# Sheet.net
KiCad netlist of a schematic drawn in Altium Designer
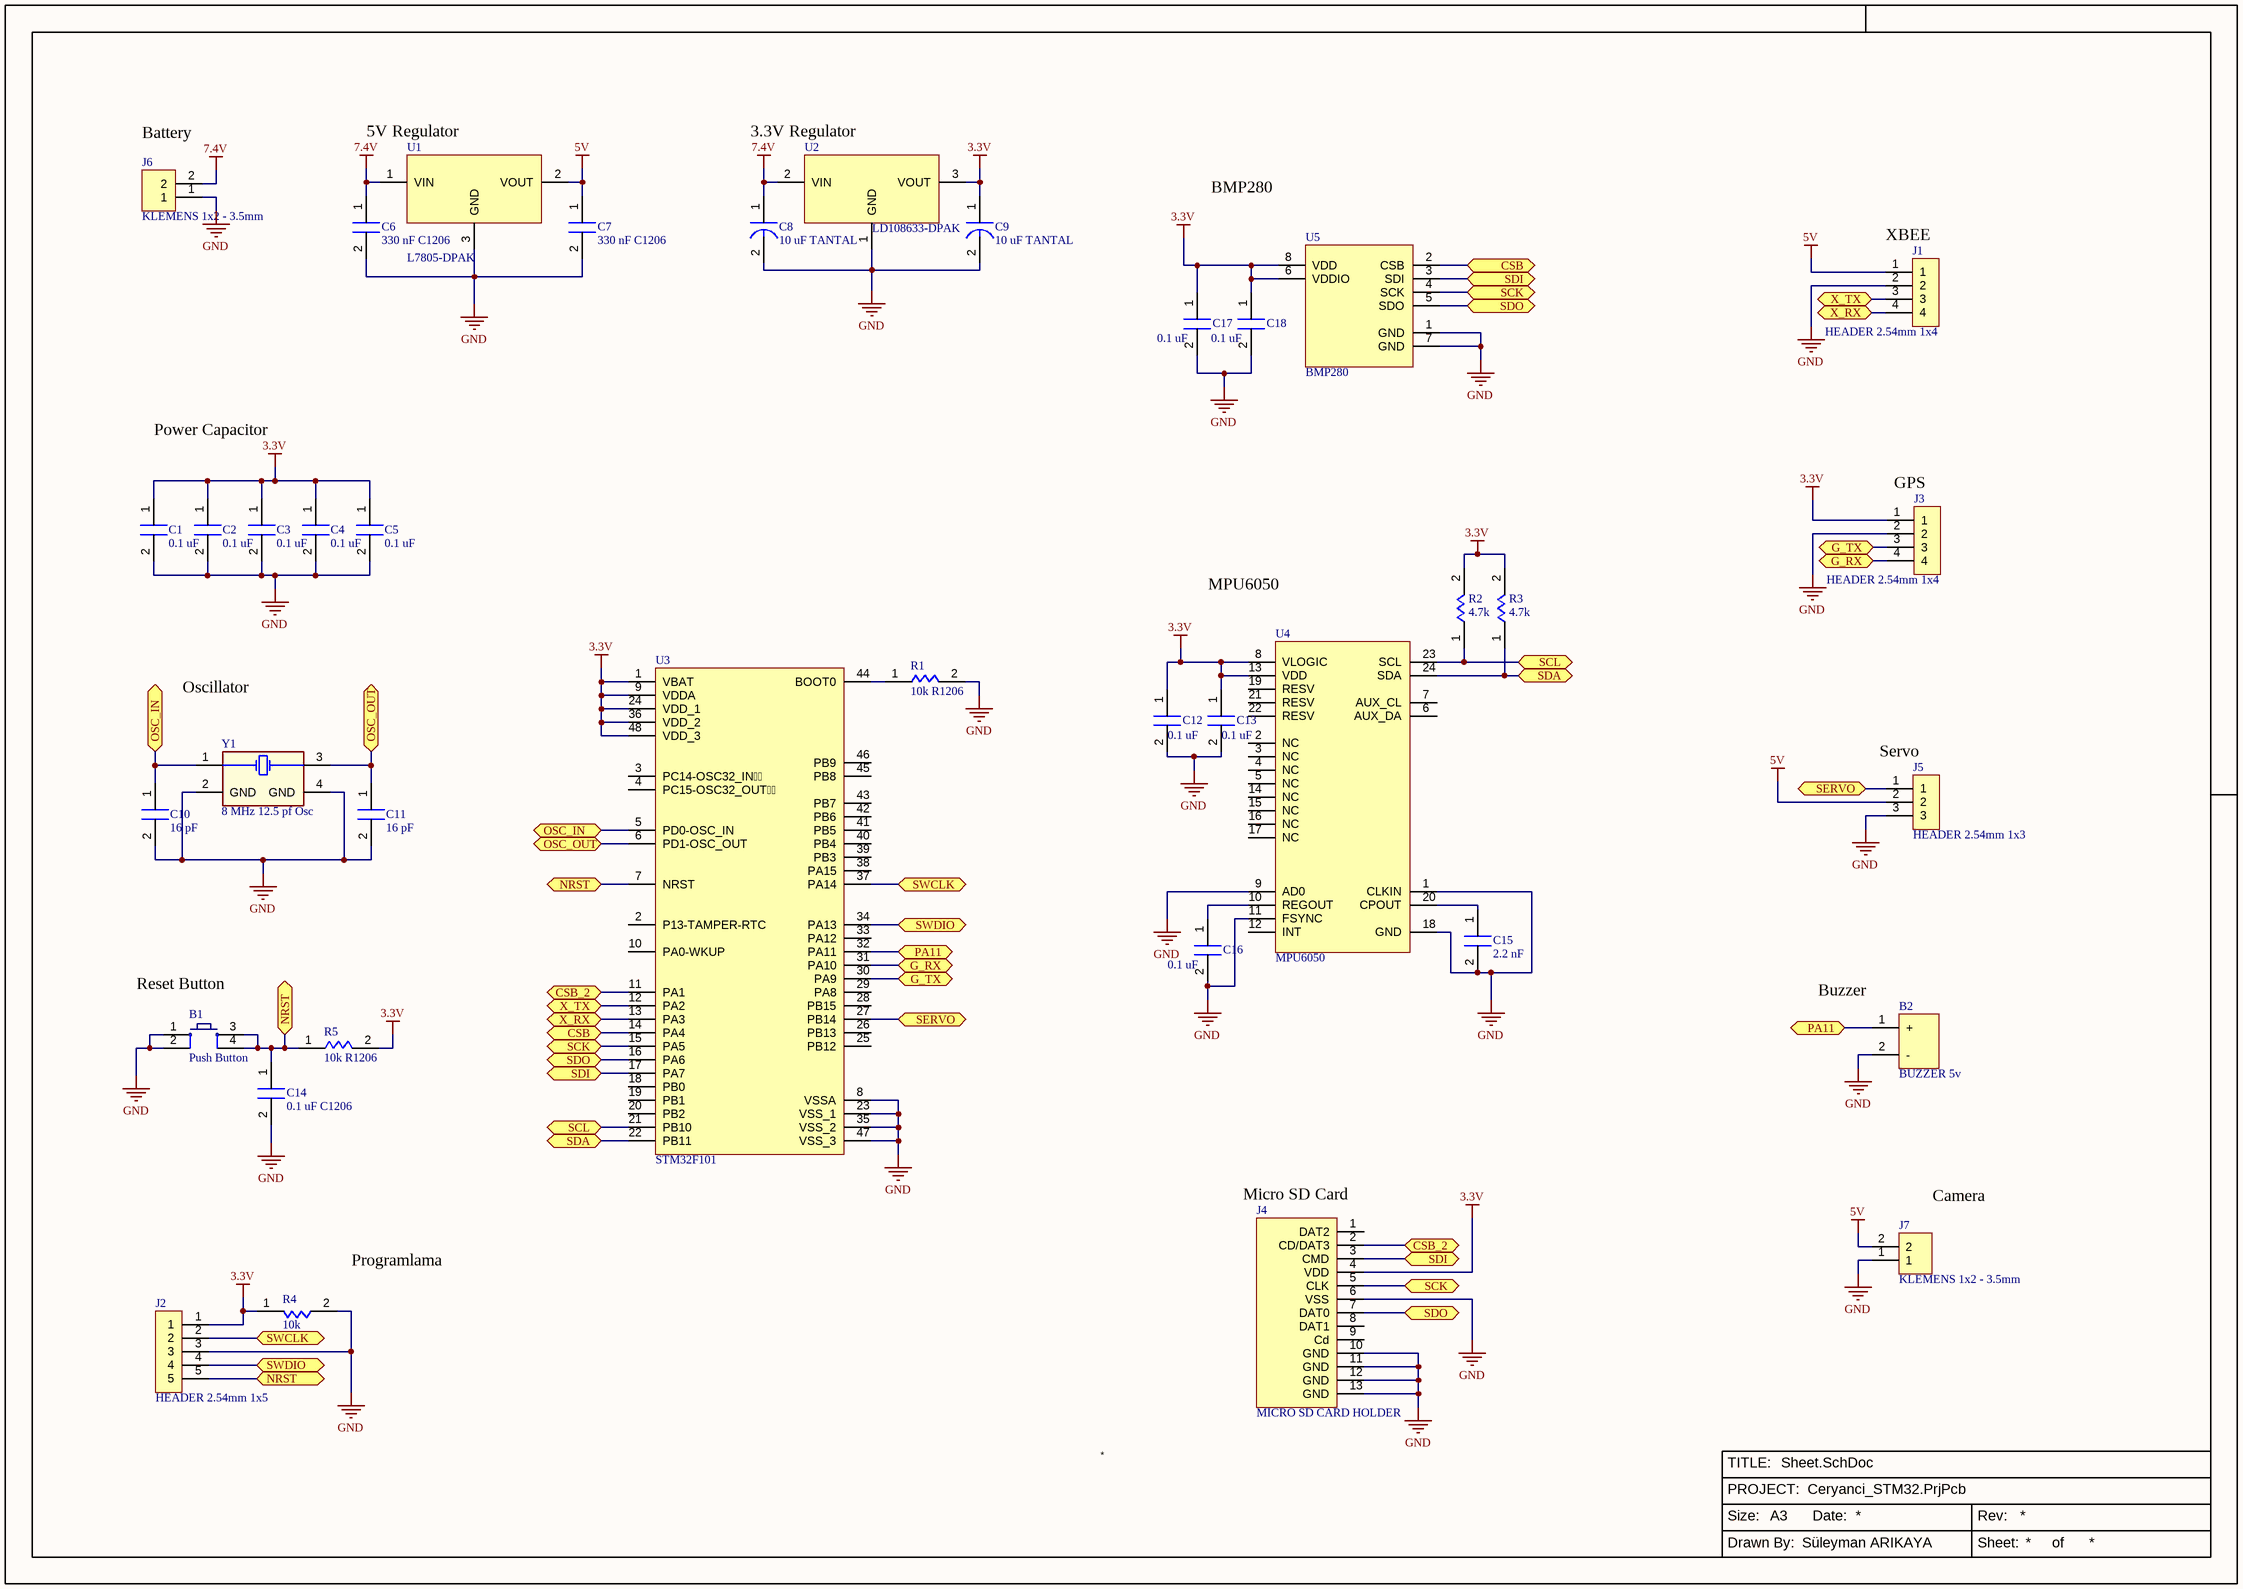
[diagram p0: Sheet.SchDoc]

(export (version "E")
  (design (tool "Eeschema 10.0.6"))
  (components
    (comp (ref "B1")
      (value "Push Button")
      (footprint "PUSB BUTTON-SMD")
      (description "Smd Push Button")
      (libsource (lib "STM32") (part "Push Button"))
    )
    (comp (ref "B2") (value "BUZZER 5v") (footprint "BUZZER 5v") (libsource (lib "STM32") (part "BUZZER 5v")))
    (comp (ref "C1")
      (value "0.1 uF")
      (footprint "C1206")
      (description "0.1 uF C1206")
      (libsource (lib "STM32") (part "0.1 uF C1206"))
    )
    (comp (ref "C2")
      (value "0.1 uF")
      (footprint "C1206")
      (description "0.1 uF C1206")
      (libsource (lib "STM32") (part "0.1 uF C1206"))
    )
    (comp (ref "C3")
      (value "0.1 uF")
      (footprint "C1206")
      (description "0.1 uF C1206")
      (libsource (lib "STM32") (part "0.1 uF C1206"))
    )
    (comp (ref "C4")
      (value "0.1 uF")
      (footprint "C1206")
      (description "0.1 uF C1206")
      (libsource (lib "STM32") (part "0.1 uF C1206"))
    )
    (comp (ref "C5")
      (value "0.1 uF")
      (footprint "C1206")
      (description "0.1 uF C1206")
      (libsource (lib "STM32") (part "0.1 uF C1206"))
    )
    (comp (ref "C6")
      (value "330 nF C1206")
      (footprint "C1206")
      (libsource (lib "STM32") (part "330 nF C1206"))
    )
    (comp (ref "C7")
      (value "330 nF C1206")
      (footprint "C1206")
      (libsource (lib "STM32") (part "330 nF C1206"))
    )
    (comp (ref "C8")
      (value "10 uF TANTAL")
      (footprint "C1206 - TANTAL")
      (description "10 uF C1206 - TANTAL")
      (libsource (lib "STM32") (part "10 uF TANTAL"))
    )
    (comp (ref "C9")
      (value "10 uF TANTAL")
      (footprint "C1206 - TANTAL")
      (description "10 uF C1206 - TANTAL")
      (libsource (lib "STM32") (part "10 uF TANTAL"))
    )
    (comp (ref "C10") (value "16 pF") (footprint "C1206") (libsource (lib "STM32") (part "16 pF")))
    (comp (ref "C11") (value "16 pF") (footprint "C1206") (libsource (lib "STM32") (part "16 pF")))
    (comp (ref "C12")
      (value "0.1 uF")
      (footprint "C1206")
      (description "0.1 uF C1206")
      (libsource (lib "STM32") (part "0.1 uF C1206"))
    )
    (comp (ref "C13")
      (value "0.1 uF")
      (footprint "C1206")
      (description "0.1 uF C1206")
      (libsource (lib "STM32") (part "0.1 uF C1206"))
    )
    (comp (ref "C14")
      (value "0.1 uF C1206")
      (footprint "C1206")
      (libsource (lib "STM32") (part "0.1 uF C1206"))
    )
    (comp (ref "C15")
      (value "2.2 nF")
      (footprint "C1206")
      (description "2.2 nF C1206")
      (libsource (lib "STM32") (part "2.2 nF"))
    )
    (comp (ref "C16")
      (value "0.1 uF")
      (footprint "C1206")
      (description "0.1 uF C1206")
      (libsource (lib "STM32") (part "0.1 uF C1206"))
    )
    (comp (ref "C17")
      (value "0.1 uF")
      (footprint "C1206")
      (description "0.1 uF C1206")
      (libsource (lib "STM32") (part "0.1 uF C1206"))
    )
    (comp (ref "C18")
      (value "0.1 uF")
      (footprint "C1206")
      (description "0.1 uF C1206")
      (libsource (lib "STM32") (part "0.1 uF C1206"))
    )
    (comp (ref "J1")
      (value "HEADER 2.54mm 1x4")
      (footprint "HEADER 2.54mm 1x4")
      (libsource (lib "STM32") (part "HEADER 2.54mm 1x4"))
    )
    (comp (ref "J2")
      (value "HEADER 2.54mm 1x5")
      (footprint "HEADER 2.54mm 1x5")
      (libsource (lib "STM32") (part "HEADER 2.54mm 1x5"))
    )
    (comp (ref "J3")
      (value "HEADER 2.54mm 1x4")
      (footprint "HEADER 2.54mm 1x4")
      (libsource (lib "STM32") (part "HEADER 2.54mm 1x4"))
    )
    (comp (ref "J4")
      (value "MICRO SD CARD HOLDER")
      (footprint "MICRO SD CARD HOLDER")
      (description "MICRO SD CARD HOLDER KLS1-TF-003 Micro SD Card Connector")
      (libsource (lib "STM32") (part "MICRO SD CARD HOLDER"))
    )
    (comp (ref "J5")
      (value "HEADER 2.54mm 1x3")
      (footprint "HEADER 2.54mm 1x3")
      (libsource (lib "STM32") (part "HEADER 2.54mm 1x3"))
    )
    (comp (ref "J6")
      (value "KLEMENS 1x2 - 3.5mm")
      (footprint "KLEMENS 1x2 - 3.5mm")
      (libsource (lib "") (part "KLEMENS 1x2 - 3.5mm_1"))
    )
    (comp (ref "J7")
      (value "KLEMENS 1x2 - 3.5mm")
      (footprint "KLEMENS 1x2 - 3.5mm")
      (libsource (lib "STM32") (part "KLEMENS 1x2 - 3.5mm"))
    )
    (comp (ref "R1")
      (value "10k R1206")
      (footprint "R1206 RESISTOR")
      (libsource (lib "STM32") (part "10k R1206"))
    )
    (comp (ref "R2")
      (value "4.7k")
      (footprint "R1206 RESISTOR")
      (description "4.7k R1206")
      (libsource (lib "STM32") (part "4.7k"))
    )
    (comp (ref "R3")
      (value "4.7k")
      (footprint "R1206 RESISTOR")
      (description "4.7k R1206")
      (libsource (lib "STM32") (part "4.7k"))
    )
    (comp (ref "R4")
      (value "10k")
      (footprint "R1206 RESISTOR")
      (description "10k R1206")
      (libsource (lib "STM32") (part "10k"))
    )
    (comp (ref "R5")
      (value "10k R1206")
      (footprint "R1206 RESISTOR")
      (libsource (lib "STM32") (part "10k R1206"))
    )
    (comp (ref "U1")
      (value "L7805-DPAK")
      (footprint "DPAK228P972X240-3N")
      (description "L7805 5V REGULATOR SMD PACKET")
      (libsource (lib "STM32") (part "L7805-DPAK"))
    )
    (comp (ref "U2")
      (value "LD108633-DPAK")
      (footprint "DPAK228P972X240-3N")
      (description "LD108633 3.3V REGULATOR DPAK")
      (libsource (lib "STM32") (part "LD108633-DPAK"))
    )
    (comp (ref "U3")
      (value "STM32F101")
      (footprint "LQPF48_STM")
      (description "STM32F101 48PIN MICROPROCESSOR")
      (libsource (lib "STM32") (part "STM32F101"))
    )
    (comp (ref "U4")
      (value "MPU6050")
      (footprint "QFN50P400X400X95_HS-25N")
      (description "MPU GYRO")
      (libsource (lib "STM32") (part "MPU6050"))
    )
    (comp (ref "U5")
      (value "BMP280")
      (footprint "BMP280")
      (description "BMP280 PRESSURE")
      (libsource (lib "STM32") (part "BMP280"))
    )
    (comp (ref "Y1")
      (value "8 MHz 12.5 pf Osc")
      (footprint "8 MHZ Osc.")
      (libsource (lib "STM32") (part "8 MHz 12.5 pf Osc"))
    )
  )
  (nets
    (net (code "1") (name "/CSB") (class "Default")
      (node (ref "U3") (pin "14") (pinfunction "PA4_14") (pintype "passive"))
      (node (ref "U5") (pin "2") (pinfunction "CSB_2") (pintype "passive"))
    )
    (net (code "2") (name "/CSB_2") (class "Default")
      (node (ref "J4") (pin "2") (pinfunction "CD/DAT3_2") (pintype "passive"))
      (node (ref "U3") (pin "11") (pinfunction "PA1_11") (pintype "passive"))
    )
    (net (code "3") (name "/G_RX") (class "Default")
      (node (ref "J3") (pin "4") (pinfunction "4_4") (pintype "passive"))
      (node (ref "U3") (pin "31") (pinfunction "PA10_31") (pintype "passive"))
    )
    (net (code "4") (name "/G_TX") (class "Default")
      (node (ref "J3") (pin "3") (pinfunction "3_3") (pintype "passive"))
      (node (ref "U3") (pin "30") (pinfunction "PA9_30") (pintype "passive"))
    )
    (net (code "5") (name "/NRST") (class "Default")
      (node (ref "B1") (pin "3") (pinfunction "3_3") (pintype "passive"))
      (node (ref "B1") (pin "4") (pinfunction "4_4") (pintype "passive"))
      (node (ref "C14") (pin "1") (pinfunction "1_1") (pintype "passive"))
      (node (ref "J2") (pin "5") (pinfunction "5_5") (pintype "passive"))
      (node (ref "R5") (pin "1") (pinfunction "1_1") (pintype "passive"))
      (node (ref "U3") (pin "7") (pinfunction "NRST_7") (pintype "passive"))
    )
    (net (code "6") (name "/OSC_IN") (class "Default")
      (node (ref "C10") (pin "1") (pinfunction "1_1") (pintype "passive"))
      (node (ref "U3") (pin "5") (pinfunction "PD0-OSC_IN_5") (pintype "passive"))
      (node (ref "Y1") (pin "1") (pintype "passive"))
    )
    (net (code "7") (name "/OSC_OUT") (class "Default")
      (node (ref "C11") (pin "1") (pinfunction "1_1") (pintype "passive"))
      (node (ref "U3") (pin "6") (pinfunction "PD1-OSC_OUT_6") (pintype "passive"))
      (node (ref "Y1") (pin "3") (pintype "passive"))
    )
    (net (code "8") (name "/PA11") (class "Default")
      (node (ref "B2") (pin "1") (pinfunction "+_1") (pintype "passive"))
      (node (ref "U3") (pin "32") (pinfunction "PA11_32") (pintype "passive"))
    )
    (net (code "9") (name "/SCK") (class "Default")
      (node (ref "J4") (pin "5") (pinfunction "CLK_5") (pintype "passive"))
      (node (ref "U3") (pin "15") (pinfunction "PA5_15") (pintype "passive"))
      (node (ref "U5") (pin "4") (pinfunction "SCK_4") (pintype "passive"))
    )
    (net (code "10") (name "/SCL") (class "Default")
      (node (ref "R2") (pin "1") (pinfunction "1_1") (pintype "passive"))
      (node (ref "U3") (pin "21") (pinfunction "PB10_21") (pintype "passive"))
      (node (ref "U4") (pin "23") (pinfunction "SCL_23") (pintype "passive"))
    )
    (net (code "11") (name "/SDA") (class "Default")
      (node (ref "R3") (pin "1") (pinfunction "1_1") (pintype "passive"))
      (node (ref "U3") (pin "22") (pinfunction "PB11_22") (pintype "passive"))
      (node (ref "U4") (pin "24") (pinfunction "SDA_24") (pintype "passive"))
    )
    (net (code "12") (name "/SDI") (class "Default")
      (node (ref "J4") (pin "3") (pinfunction "CMD_3") (pintype "passive"))
      (node (ref "U3") (pin "17") (pinfunction "PA7_17") (pintype "passive"))
      (node (ref "U5") (pin "3") (pinfunction "SDI_3") (pintype "passive"))
    )
    (net (code "13") (name "/SDO") (class "Default")
      (node (ref "J4") (pin "7") (pinfunction "DAT0_7") (pintype "passive"))
      (node (ref "U3") (pin "16") (pinfunction "PA6_16") (pintype "passive"))
      (node (ref "U5") (pin "5") (pinfunction "SDO_5") (pintype "passive"))
    )
    (net (code "14") (name "/SERVO") (class "Default")
      (node (ref "J5") (pin "1") (pinfunction "1_1") (pintype "passive"))
      (node (ref "U3") (pin "27") (pinfunction "PB14_27") (pintype "passive"))
    )
    (net (code "15") (name "/SWCLK") (class "Default")
      (node (ref "J2") (pin "2") (pinfunction "2_2") (pintype "passive"))
      (node (ref "U3") (pin "37") (pinfunction "PA14_37") (pintype "passive"))
    )
    (net (code "16") (name "/SWDIO") (class "Default")
      (node (ref "J2") (pin "4") (pinfunction "4_4") (pintype "passive"))
      (node (ref "U3") (pin "34") (pinfunction "PA13_34") (pintype "passive"))
    )
    (net (code "17") (name "/X_RX") (class "Default")
      (node (ref "J1") (pin "4") (pinfunction "4_4") (pintype "passive"))
      (node (ref "U3") (pin "13") (pinfunction "PA3_13") (pintype "passive"))
    )
    (net (code "18") (name "/X_TX") (class "Default")
      (node (ref "J1") (pin "3") (pinfunction "3_3") (pintype "passive"))
      (node (ref "U3") (pin "12") (pinfunction "PA2_12") (pintype "passive"))
    )
    (net (code "19") (name "3.3V") (class "Default")
      (node (ref "C1") (pin "1") (pinfunction "1_1") (pintype "passive"))
      (node (ref "C12") (pin "1") (pinfunction "1_1") (pintype "passive"))
      (node (ref "C13") (pin "1") (pinfunction "1_1") (pintype "passive"))
      (node (ref "C17") (pin "1") (pinfunction "1_1") (pintype "passive"))
      (node (ref "C18") (pin "1") (pinfunction "1_1") (pintype "passive"))
      (node (ref "C2") (pin "1") (pinfunction "1_1") (pintype "passive"))
      (node (ref "C3") (pin "1") (pinfunction "1_1") (pintype "passive"))
      (node (ref "C4") (pin "1") (pinfunction "1_1") (pintype "passive"))
      (node (ref "C5") (pin "1") (pinfunction "1_1") (pintype "passive"))
      (node (ref "C9") (pin "1") (pinfunction "1_1") (pintype "passive"))
      (node (ref "J2") (pin "1") (pinfunction "1_1") (pintype "passive"))
      (node (ref "J3") (pin "1") (pinfunction "1_1") (pintype "passive"))
      (node (ref "J4") (pin "4") (pinfunction "VDD_4") (pintype "passive"))
      (node (ref "R2") (pin "2") (pinfunction "2_2") (pintype "passive"))
      (node (ref "R3") (pin "2") (pinfunction "2_2") (pintype "passive"))
      (node (ref "R4") (pin "1") (pinfunction "1_1") (pintype "passive"))
      (node (ref "R5") (pin "2") (pinfunction "2_2") (pintype "passive"))
      (node (ref "U2") (pin "3") (pinfunction "VOUT_3") (pintype "passive"))
      (node (ref "U3") (pin "1") (pinfunction "VBAT_1") (pintype "passive"))
      (node (ref "U3") (pin "24") (pinfunction "VDD_1_24") (pintype "passive"))
      (node (ref "U3") (pin "36") (pinfunction "VDD_2_36") (pintype "passive"))
      (node (ref "U3") (pin "48") (pinfunction "VDD_3_48") (pintype "passive"))
      (node (ref "U3") (pin "9") (pinfunction "VDDA_9") (pintype "passive"))
      (node (ref "U4") (pin "13") (pinfunction "VDD_13") (pintype "passive"))
      (node (ref "U4") (pin "8") (pinfunction "VLOGIC_8") (pintype "passive"))
      (node (ref "U5") (pin "6") (pinfunction "VDDIO_6") (pintype "passive"))
      (node (ref "U5") (pin "8") (pinfunction "VDD_8") (pintype "passive"))
    )
    (net (code "20") (name "5V") (class "Default")
      (node (ref "C7") (pin "1") (pinfunction "1_1") (pintype "passive"))
      (node (ref "J1") (pin "1") (pinfunction "1_1") (pintype "passive"))
      (node (ref "J5") (pin "2") (pinfunction "2_2") (pintype "passive"))
      (node (ref "J7") (pin "2") (pinfunction "2_2") (pintype "passive"))
      (node (ref "U1") (pin "2") (pinfunction "VOUT_2") (pintype "passive"))
    )
    (net (code "21") (name "7.4V") (class "Default")
      (node (ref "C6") (pin "1") (pinfunction "1_1") (pintype "passive"))
      (node (ref "C8") (pin "1") (pinfunction "1_1") (pintype "passive"))
      (node (ref "J6") (pin "2") (pinfunction "2_2") (pintype "passive"))
      (node (ref "U1") (pin "1") (pinfunction "VIN_1") (pintype "passive"))
      (node (ref "U2") (pin "2") (pinfunction "VIN_2") (pintype "passive"))
    )
    (net (code "22") (name "GND") (class "Default")
      (node (ref "B1") (pin "1") (pinfunction "1_1") (pintype "passive"))
      (node (ref "B1") (pin "2") (pinfunction "2_2") (pintype "passive"))
      (node (ref "B2") (pin "2") (pinfunction "-_2") (pintype "passive"))
      (node (ref "C1") (pin "2") (pinfunction "2_2") (pintype "passive"))
      (node (ref "C10") (pin "2") (pinfunction "2_2") (pintype "passive"))
      (node (ref "C11") (pin "2") (pinfunction "2_2") (pintype "passive"))
      (node (ref "C12") (pin "2") (pinfunction "2_2") (pintype "passive"))
      (node (ref "C13") (pin "2") (pinfunction "2_2") (pintype "passive"))
      (node (ref "C14") (pin "2") (pinfunction "2_2") (pintype "passive"))
      (node (ref "C15") (pin "2") (pinfunction "2_2") (pintype "passive"))
      (node (ref "C16") (pin "2") (pinfunction "2_2") (pintype "passive"))
      (node (ref "C17") (pin "2") (pinfunction "2_2") (pintype "passive"))
      (node (ref "C18") (pin "2") (pinfunction "2_2") (pintype "passive"))
      (node (ref "C2") (pin "2") (pinfunction "2_2") (pintype "passive"))
      (node (ref "C3") (pin "2") (pinfunction "2_2") (pintype "passive"))
      (node (ref "C4") (pin "2") (pinfunction "2_2") (pintype "passive"))
      (node (ref "C5") (pin "2") (pinfunction "2_2") (pintype "passive"))
      (node (ref "C6") (pin "2") (pinfunction "2_2") (pintype "passive"))
      (node (ref "C7") (pin "2") (pinfunction "2_2") (pintype "passive"))
      (node (ref "C8") (pin "2") (pinfunction "2_2") (pintype "passive"))
      (node (ref "C9") (pin "2") (pinfunction "2_2") (pintype "passive"))
      (node (ref "J1") (pin "2") (pinfunction "2_2") (pintype "passive"))
      (node (ref "J2") (pin "3") (pinfunction "3_3") (pintype "passive"))
      (node (ref "J3") (pin "2") (pinfunction "2_2") (pintype "passive"))
      (node (ref "J4") (pin "10") (pinfunction "GND_10") (pintype "passive"))
      (node (ref "J4") (pin "11") (pinfunction "GND_11") (pintype "passive"))
      (node (ref "J4") (pin "12") (pinfunction "GND_12") (pintype "passive"))
      (node (ref "J4") (pin "13") (pinfunction "GND_13") (pintype "passive"))
      (node (ref "J4") (pin "6") (pinfunction "VSS_6") (pintype "passive"))
      (node (ref "J5") (pin "3") (pinfunction "3_3") (pintype "passive"))
      (node (ref "J6") (pin "1") (pinfunction "1_1") (pintype "passive"))
      (node (ref "J7") (pin "1") (pinfunction "1_1") (pintype "passive"))
      (node (ref "R1") (pin "2") (pinfunction "2_2") (pintype "passive"))
      (node (ref "R4") (pin "2") (pinfunction "2_2") (pintype "passive"))
      (node (ref "U1") (pin "3") (pinfunction "GND_3") (pintype "passive"))
      (node (ref "U2") (pin "1") (pinfunction "GND_1") (pintype "passive"))
      (node (ref "U3") (pin "23") (pinfunction "VSS_1_23") (pintype "passive"))
      (node (ref "U3") (pin "35") (pinfunction "VSS_2_35") (pintype "passive"))
      (node (ref "U3") (pin "47") (pinfunction "VSS_3_47") (pintype "passive"))
      (node (ref "U3") (pin "8") (pinfunction "VSSA_8") (pintype "passive"))
      (node (ref "U4") (pin "1") (pinfunction "CLKIN_1") (pintype "passive"))
      (node (ref "U4") (pin "11") (pinfunction "FSYNC_11") (pintype "passive"))
      (node (ref "U4") (pin "18") (pinfunction "GND_18") (pintype "passive"))
      (node (ref "U4") (pin "9") (pinfunction "AD0_9") (pintype "passive"))
      (node (ref "U5") (pin "1") (pinfunction "GND_1") (pintype "passive"))
      (node (ref "U5") (pin "7") (pinfunction "GND_7") (pintype "passive"))
      (node (ref "Y1") (pin "2") (pinfunction "GND_2") (pintype "power_in"))
      (node (ref "Y1") (pin "4") (pinfunction "GND_4") (pintype "passive"))
    )
    (net (code "23") (name "Net-(U3-BOOT0)") (class "Default")
      (node (ref "R1") (pin "1") (pinfunction "1_1") (pintype "passive"))
      (node (ref "U3") (pin "44") (pinfunction "BOOT0_44") (pintype "passive"))
    )
    (net (code "24") (name "Net-(U4-CPOUT)") (class "Default")
      (node (ref "C15") (pin "1") (pinfunction "1_1") (pintype "passive"))
      (node (ref "U4") (pin "20") (pinfunction "CPOUT_20") (pintype "passive"))
    )
    (net (code "25") (name "Net-(U4-REGOUT)") (class "Default")
      (node (ref "C16") (pin "1") (pinfunction "1_1") (pintype "passive"))
      (node (ref "U4") (pin "10") (pinfunction "REGOUT_10") (pintype "passive"))
    )
    (net (code "26") (name "unconnected-(J4-Cd-Pad9)") (class "Default")
      (node (ref "J4") (pin "9") (pinfunction "Cd_9") (pintype "passive"))
    )
    (net (code "27") (name "unconnected-(J4-DAT1-Pad8)") (class "Default")
      (node (ref "J4") (pin "8") (pinfunction "DAT1_8") (pintype "passive"))
    )
    (net (code "28") (name "unconnected-(J4-DAT2-Pad1)") (class "Default")
      (node (ref "J4") (pin "1") (pinfunction "DAT2_1") (pintype "passive"))
    )
    (net (code "29") (name "unconnected-(U3-P13-TAMPER-RTC-Pad2)") (class "Default")
      (node (ref "U3") (pin "2") (pinfunction "P13-TAMPER-RTC_2") (pintype "passive"))
    )
    (net (code "30") (name "unconnected-(U3-PA0-WKUP-Pad10)") (class "Default")
      (node (ref "U3") (pin "10") (pinfunction "PA0-WKUP_10") (pintype "passive"))
    )
    (net (code "31") (name "unconnected-(U3-PA8-Pad29)") (class "Default")
      (node (ref "U3") (pin "29") (pinfunction "PA8_29") (pintype "passive"))
    )
    (net (code "32") (name "unconnected-(U3-PA12-Pad33)") (class "Default")
      (node (ref "U3") (pin "33") (pinfunction "PA12_33") (pintype "passive"))
    )
    (net (code "33") (name "unconnected-(U3-PA15-Pad38)") (class "Default")
      (node (ref "U3") (pin "38") (pinfunction "PA15_38") (pintype "passive"))
    )
    (net (code "34") (name "unconnected-(U3-PB0-Pad18)") (class "Default")
      (node (ref "U3") (pin "18") (pinfunction "PB0_18") (pintype "passive"))
    )
    (net (code "35") (name "unconnected-(U3-PB1-Pad19)") (class "Default")
      (node (ref "U3") (pin "19") (pinfunction "PB1_19") (pintype "passive"))
    )
    (net (code "36") (name "unconnected-(U3-PB2-Pad20)") (class "Default")
      (node (ref "U3") (pin "20") (pinfunction "PB2_20") (pintype "passive"))
    )
    (net (code "37") (name "unconnected-(U3-PB3-Pad39)") (class "Default")
      (node (ref "U3") (pin "39") (pinfunction "PB3_39") (pintype "passive"))
    )
    (net (code "38") (name "unconnected-(U3-PB4-Pad40)") (class "Default")
      (node (ref "U3") (pin "40") (pinfunction "PB4_40") (pintype "passive"))
    )
    (net (code "39") (name "unconnected-(U3-PB5-Pad41)") (class "Default")
      (node (ref "U3") (pin "41") (pinfunction "PB5_41") (pintype "passive"))
    )
    (net (code "40") (name "unconnected-(U3-PB6-Pad42)") (class "Default")
      (node (ref "U3") (pin "42") (pinfunction "PB6_42") (pintype "passive"))
    )
    (net (code "41") (name "unconnected-(U3-PB7-Pad43)") (class "Default")
      (node (ref "U3") (pin "43") (pinfunction "PB7_43") (pintype "passive"))
    )
    (net (code "42") (name "unconnected-(U3-PB8-Pad45)") (class "Default")
      (node (ref "U3") (pin "45") (pinfunction "PB8_45") (pintype "passive"))
    )
    (net (code "43") (name "unconnected-(U3-PB9-Pad46)") (class "Default")
      (node (ref "U3") (pin "46") (pinfunction "PB9_46") (pintype "passive"))
    )
    (net (code "44") (name "unconnected-(U3-PB12-Pad25)") (class "Default")
      (node (ref "U3") (pin "25") (pinfunction "PB12_25") (pintype "passive"))
    )
    (net (code "45") (name "unconnected-(U3-PB13-Pad26)") (class "Default")
      (node (ref "U3") (pin "26") (pinfunction "PB13_26") (pintype "passive"))
    )
    (net (code "46") (name "unconnected-(U3-PB15-Pad28)") (class "Default")
      (node (ref "U3") (pin "28") (pinfunction "PB15_28") (pintype "passive"))
    )
    (net (code "47") (name "unconnected-(U3-PC14-OSC32_IN-Pad3)") (class "Default")
      (node (ref "U3") (pin "3") (pinfunction "PC14-OSC32_IN_3") (pintype "passive"))
    )
    (net (code "48") (name "unconnected-(U3-PC15-OSC32_OUT-Pad4)") (class "Default")
      (node (ref "U3") (pin "4") (pinfunction "PC15-OSC32_OUT_4") (pintype "passive"))
    )
    (net (code "49") (name "unconnected-(U4-AUX_CL-Pad7)") (class "Default")
      (node (ref "U4") (pin "7") (pinfunction "AUX_CL_7") (pintype "passive"))
    )
    (net (code "50") (name "unconnected-(U4-AUX_DA-Pad6)") (class "Default")
      (node (ref "U4") (pin "6") (pinfunction "AUX_DA_6") (pintype "passive"))
    )
    (net (code "51") (name "unconnected-(U4-INT-Pad12)") (class "Default")
      (node (ref "U4") (pin "12") (pinfunction "INT_12") (pintype "passive"))
    )
    (net (code "52") (name "unconnected-(U4-NC-Pad2)") (class "Default")
      (node (ref "U4") (pin "2") (pinfunction "NC_2") (pintype "passive"))
    )
    (net (code "53") (name "unconnected-(U4-NC-Pad3)") (class "Default")
      (node (ref "U4") (pin "3") (pinfunction "NC_3") (pintype "passive"))
    )
    (net (code "54") (name "unconnected-(U4-NC-Pad4)") (class "Default")
      (node (ref "U4") (pin "4") (pinfunction "NC_4") (pintype "passive"))
    )
    (net (code "55") (name "unconnected-(U4-NC-Pad5)") (class "Default")
      (node (ref "U4") (pin "5") (pinfunction "NC_5") (pintype "passive"))
    )
    (net (code "56") (name "unconnected-(U4-NC-Pad14)") (class "Default")
      (node (ref "U4") (pin "14") (pinfunction "NC_14") (pintype "passive"))
    )
    (net (code "57") (name "unconnected-(U4-NC-Pad15)") (class "Default")
      (node (ref "U4") (pin "15") (pinfunction "NC_15") (pintype "passive"))
    )
    (net (code "58") (name "unconnected-(U4-NC-Pad16)") (class "Default")
      (node (ref "U4") (pin "16") (pinfunction "NC_16") (pintype "passive"))
    )
    (net (code "59") (name "unconnected-(U4-NC-Pad17)") (class "Default")
      (node (ref "U4") (pin "17") (pinfunction "NC_17") (pintype "passive"))
    )
    (net (code "60") (name "unconnected-(U4-RESV-Pad19)") (class "Default")
      (node (ref "U4") (pin "19") (pinfunction "RESV_19") (pintype "passive"))
    )
    (net (code "61") (name "unconnected-(U4-RESV-Pad21)") (class "Default")
      (node (ref "U4") (pin "21") (pinfunction "RESV_21") (pintype "passive"))
    )
    (net (code "62") (name "unconnected-(U4-RESV-Pad22)") (class "Default")
      (node (ref "U4") (pin "22") (pinfunction "RESV_22") (pintype "passive"))
    )
  )
)
